# POWER.net
KiCad netlist of a schematic drawn in Altium Designer
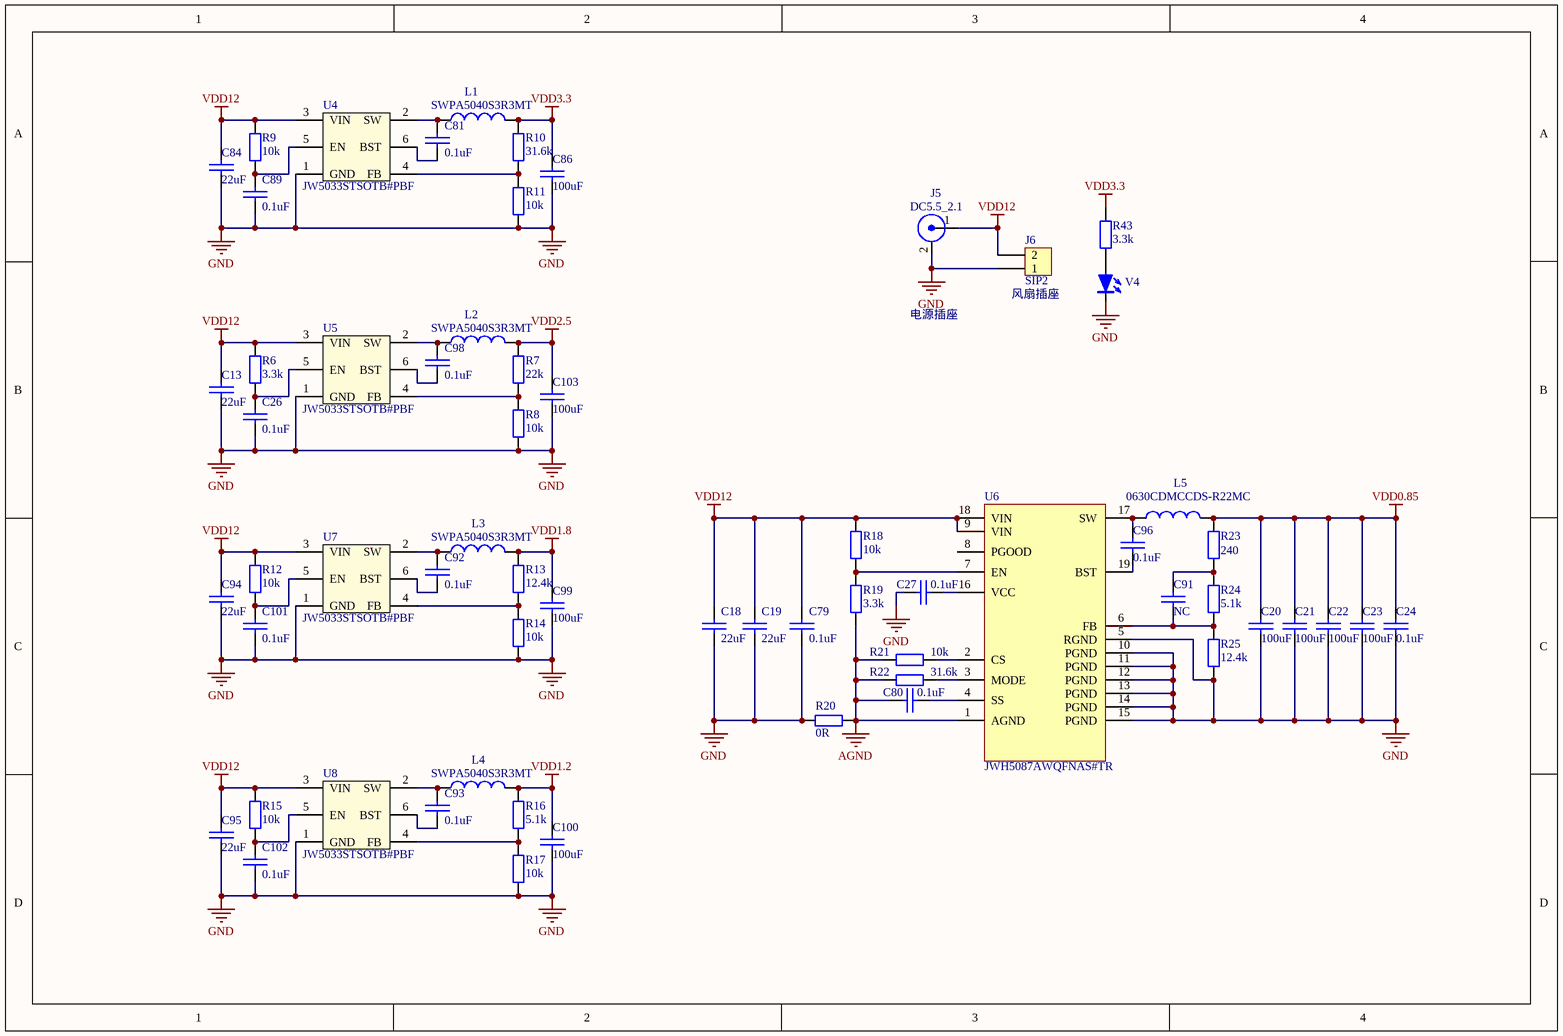
[diagram p0: POWER.SchDoc]

(export (version "E")
  (design (tool "Eeschema 10.0.6"))
  (components
    (comp (ref "C13") (value "22uF") (footprint "1210_C_M") (libsource (lib "Component") (part "CAP")))
    (comp (ref "C18") (value "22uF") (footprint "1210_C_M") (libsource (lib "Component") (part "CAP")))
    (comp (ref "C19") (value "22uF") (footprint "1210_C_M") (libsource (lib "Component") (part "CAP")))
    (comp (ref "C20") (value "100uF") (footprint "1210_C_M") (libsource (lib "Component") (part "CAP")))
    (comp (ref "C21") (value "100uF") (footprint "1210_C_M") (libsource (lib "Component") (part "CAP")))
    (comp (ref "C22") (value "100uF") (footprint "1210_C_M") (libsource (lib "Component") (part "CAP")))
    (comp (ref "C23") (value "100uF") (footprint "1210_C_M") (libsource (lib "Component") (part "CAP")))
    (comp (ref "C24") (value "0.1uF") (footprint "0402_C_M") (libsource (lib "Component") (part "CAP")))
    (comp (ref "C26") (value "0.1uF") (footprint "0402_C_M") (libsource (lib "Component") (part "CAP")))
    (comp (ref "C27") (value "0.1uF") (footprint "0402_C_M") (libsource (lib "Component") (part "CAP")))
    (comp (ref "C79") (value "0.1uF") (footprint "0402_C_M") (libsource (lib "Component") (part "CAP")))
    (comp (ref "C80") (value "0.1uF") (footprint "0402_C_M") (libsource (lib "Component") (part "CAP")))
    (comp (ref "C81") (value "0.1uF") (footprint "0402_C_M") (libsource (lib "Component") (part "CAP")))
    (comp (ref "C84") (value "22uF") (footprint "1210_C_M") (libsource (lib "Component") (part "CAP")))
    (comp (ref "C86") (value "100uF") (footprint "1210_C_M") (libsource (lib "Component") (part "CAP")))
    (comp (ref "C89") (value "0.1uF") (footprint "0402_C_M") (libsource (lib "Component") (part "CAP")))
    (comp (ref "C91") (value "NC") (footprint "0402_C_M") (libsource (lib "Component") (part "CAP")))
    (comp (ref "C92") (value "0.1uF") (footprint "0402_C_M") (libsource (lib "Component") (part "CAP")))
    (comp (ref "C93") (value "0.1uF") (footprint "0402_C_M") (libsource (lib "Component") (part "CAP")))
    (comp (ref "C94") (value "22uF") (footprint "1210_C_M") (libsource (lib "Component") (part "CAP")))
    (comp (ref "C95") (value "22uF") (footprint "1210_C_M") (libsource (lib "Component") (part "CAP")))
    (comp (ref "C96") (value "0.1uF") (footprint "0402_C_M") (libsource (lib "Component") (part "CAP")))
    (comp (ref "C98") (value "0.1uF") (footprint "0402_C_M") (libsource (lib "Component") (part "CAP")))
    (comp (ref "C99") (value "100uF") (footprint "1210_C_M") (libsource (lib "Component") (part "CAP")))
    (comp (ref "C100") (value "100uF") (footprint "1210_C_M") (libsource (lib "Component") (part "CAP")))
    (comp (ref "C101") (value "0.1uF") (footprint "0402_C_M") (libsource (lib "Component") (part "CAP")))
    (comp (ref "C102") (value "0.1uF") (footprint "0402_C_M") (libsource (lib "Component") (part "CAP")))
    (comp (ref "C103") (value "100uF") (footprint "1210_C_M") (libsource (lib "Component") (part "CAP")))
    (comp (ref "J5") (value "DC5.5_2.1") (footprint "DC5.5") (libsource (lib "常用库") (part "BNC")))
    (comp (ref "J6") (value "SIP2") (footprint "2.54mm_2p") (libsource (lib "DIP_SIP") (part "SIP2")))
    (comp (ref "L1")
      (value "SWPA5040S3R3MT")
      (footprint "CD42")
      (libsource (lib "My library") (part "INDUCTOR1"))
    )
    (comp (ref "L2")
      (value "SWPA5040S3R3MT")
      (footprint "CD42")
      (libsource (lib "My library") (part "INDUCTOR1"))
    )
    (comp (ref "L3")
      (value "SWPA5040S3R3MT")
      (footprint "CD42")
      (libsource (lib "My library") (part "INDUCTOR1"))
    )
    (comp (ref "L4")
      (value "SWPA5040S3R3MT")
      (footprint "CD42")
      (libsource (lib "My library") (part "INDUCTOR1"))
    )
    (comp (ref "L5")
      (value "0630CDMCCDS-R22MC")
      (footprint "SWPA8050S")
      (libsource (lib "My library") (part "INDUCTOR1"))
    )
    (comp (ref "R6") (value "3.3k") (footprint "0402_R_M") (libsource (lib "Common") (part "RES2")))
    (comp (ref "R7") (value "22k") (footprint "0402_R_M") (libsource (lib "Common") (part "RES2")))
    (comp (ref "R8") (value "10k") (footprint "0402_R_M") (libsource (lib "Common") (part "RES2")))
    (comp (ref "R9") (value "10k") (footprint "0402_R_M") (libsource (lib "Common") (part "RES2")))
    (comp (ref "R10") (value "31.6k") (footprint "0402_R_M") (libsource (lib "Common") (part "RES2")))
    (comp (ref "R11") (value "10k") (footprint "0402_R_M") (libsource (lib "Common") (part "RES2")))
    (comp (ref "R12") (value "10k") (footprint "0402_R_M") (libsource (lib "Common") (part "RES2")))
    (comp (ref "R13") (value "12.4k") (footprint "0402_R_M") (libsource (lib "Common") (part "RES2")))
    (comp (ref "R14") (value "10k") (footprint "0402_R_M") (libsource (lib "Common") (part "RES2")))
    (comp (ref "R15") (value "10k") (footprint "0402_R_M") (libsource (lib "Common") (part "RES2")))
    (comp (ref "R16") (value "5.1k") (footprint "0402_R_M") (libsource (lib "Common") (part "RES2")))
    (comp (ref "R17") (value "10k") (footprint "0402_R_M") (libsource (lib "Common") (part "RES2")))
    (comp (ref "R18") (value "10k") (footprint "0402_R_M") (libsource (lib "Common") (part "RES2")))
    (comp (ref "R19") (value "3.3k") (footprint "0402_R_M") (libsource (lib "Common") (part "RES2")))
    (comp (ref "R20") (value "0R") (footprint "0402_R_M") (libsource (lib "Common") (part "RES2")))
    (comp (ref "R21") (value "10k") (footprint "0402_R_M") (libsource (lib "Common") (part "RES2")))
    (comp (ref "R22") (value "31.6k") (footprint "0402_R_M") (libsource (lib "Common") (part "RES2")))
    (comp (ref "R23") (value "240") (footprint "0402_R_M") (libsource (lib "Common") (part "RES2")))
    (comp (ref "R24") (value "5.1k") (footprint "0402_R_M") (libsource (lib "Common") (part "RES2")))
    (comp (ref "R25") (value "12.4k") (footprint "0402_R_M") (libsource (lib "Common") (part "RES2")))
    (comp (ref "R43") (value "3.3k") (footprint "0402_R_M") (libsource (lib "Common") (part "RES2")))
    (comp (ref "U4")
      (value "JW5033STSOTB#PBF")
      (footprint "SOT23-6")
      (libsource (lib "XC7A35T") (part "JW5060TTSOTB#PBF"))
    )
    (comp (ref "U5")
      (value "JW5033STSOTB#PBF")
      (footprint "SOT23-6")
      (libsource (lib "XC7A35T") (part "JW5060TTSOTB#PBF"))
    )
    (comp (ref "U6") (value "JWH5087AWQFNAS#TR") (libsource (lib "POWER_1") (part "IC_JW85012")))
    (comp (ref "U7")
      (value "JW5033STSOTB#PBF")
      (footprint "SOT23-6")
      (libsource (lib "XC7A35T") (part "JW5060TTSOTB#PBF"))
    )
    (comp (ref "U8")
      (value "JW5033STSOTB#PBF")
      (footprint "SOT23-6")
      (libsource (lib "XC7A35T") (part "JW5060TTSOTB#PBF"))
    )
    (comp (ref "V4") (value "LED") (footprint "0805D") (libsource (lib "发光管、数码管") (part "LED2")))
  )
  (nets
    (net (code "1") (name "AGND") (class "Default")
      (node (ref "C80") (pin "1") (pinfunction "1_1") (pintype "passive"))
      (node (ref "R19") (pin "1") (pintype "passive"))
      (node (ref "R20") (pin "2") (pintype "passive"))
      (node (ref "R21") (pin "2") (pintype "passive"))
      (node (ref "R22") (pin "2") (pintype "passive"))
      (node (ref "U6") (pin "1") (pinfunction "AGND_1") (pintype "passive"))
    )
    (net (code "2") (name "GND") (class "Default")
      (node (ref "C100") (pin "2") (pinfunction "2_2") (pintype "passive"))
      (node (ref "C101") (pin "2") (pinfunction "2_2") (pintype "passive"))
      (node (ref "C102") (pin "2") (pinfunction "2_2") (pintype "passive"))
      (node (ref "C103") (pin "2") (pinfunction "2_2") (pintype "passive"))
      (node (ref "C13") (pin "2") (pinfunction "2_2") (pintype "passive"))
      (node (ref "C18") (pin "1") (pinfunction "1_1") (pintype "passive"))
      (node (ref "C19") (pin "1") (pinfunction "1_1") (pintype "passive"))
      (node (ref "C20") (pin "2") (pinfunction "2_2") (pintype "passive"))
      (node (ref "C21") (pin "2") (pinfunction "2_2") (pintype "passive"))
      (node (ref "C22") (pin "2") (pinfunction "2_2") (pintype "passive"))
      (node (ref "C23") (pin "2") (pinfunction "2_2") (pintype "passive"))
      (node (ref "C24") (pin "1") (pinfunction "1_1") (pintype "passive"))
      (node (ref "C26") (pin "2") (pinfunction "2_2") (pintype "passive"))
      (node (ref "C27") (pin "2") (pinfunction "2_2") (pintype "passive"))
      (node (ref "C79") (pin "2") (pinfunction "2_2") (pintype "passive"))
      (node (ref "C84") (pin "2") (pinfunction "2_2") (pintype "passive"))
      (node (ref "C86") (pin "2") (pinfunction "2_2") (pintype "passive"))
      (node (ref "C89") (pin "2") (pinfunction "2_2") (pintype "passive"))
      (node (ref "C94") (pin "2") (pinfunction "2_2") (pintype "passive"))
      (node (ref "C95") (pin "2") (pinfunction "2_2") (pintype "passive"))
      (node (ref "C99") (pin "2") (pinfunction "2_2") (pintype "passive"))
      (node (ref "J5") (pin "2") (pinfunction "2_2") (pintype "passive"))
      (node (ref "J6") (pin "1") (pinfunction "1_1") (pintype "passive"))
      (node (ref "R11") (pin "2") (pintype "passive"))
      (node (ref "R14") (pin "2") (pintype "passive"))
      (node (ref "R17") (pin "2") (pintype "passive"))
      (node (ref "R20") (pin "1") (pintype "passive"))
      (node (ref "R25") (pin "2") (pintype "passive"))
      (node (ref "R8") (pin "2") (pintype "passive"))
      (node (ref "U4") (pin "1") (pinfunction "GND_1") (pintype "passive"))
      (node (ref "U5") (pin "1") (pinfunction "GND_1") (pintype "passive"))
      (node (ref "U6") (pin "10") (pinfunction "PGND_10") (pintype "passive"))
      (node (ref "U6") (pin "11") (pinfunction "PGND_11") (pintype "passive"))
      (node (ref "U6") (pin "12") (pinfunction "PGND_12") (pintype "passive"))
      (node (ref "U6") (pin "13") (pinfunction "PGND_13") (pintype "passive"))
      (node (ref "U6") (pin "14") (pinfunction "PGND_14") (pintype "passive"))
      (node (ref "U6") (pin "15") (pinfunction "PGND_15") (pintype "passive"))
      (node (ref "U6") (pin "5") (pinfunction "RGND_5") (pintype "passive"))
      (node (ref "U7") (pin "1") (pinfunction "GND_1") (pintype "passive"))
      (node (ref "U8") (pin "1") (pinfunction "GND_1") (pintype "passive"))
      (node (ref "V4") (pin "2") (pinfunction "2_2") (pintype "passive"))
    )
    (net (code "3") (name "Net-(C91-Pad2)") (class "Default")
      (node (ref "C91") (pin "2") (pinfunction "2_2") (pintype "passive"))
      (node (ref "R23") (pin "2") (pintype "passive"))
      (node (ref "R24") (pin "1") (pintype "passive"))
    )
    (net (code "4") (name "Net-(R43-Pad1)") (class "Default")
      (node (ref "R43") (pin "1") (pintype "passive"))
      (node (ref "V4") (pin "1") (pinfunction "1_1") (pintype "passive"))
    )
    (net (code "5") (name "Net-(U4-BST)") (class "Default")
      (node (ref "C81") (pin "1") (pinfunction "1_1") (pintype "passive"))
      (node (ref "U4") (pin "6") (pinfunction "BST_6") (pintype "passive"))
    )
    (net (code "6") (name "Net-(U4-EN)") (class "Default")
      (node (ref "C89") (pin "1") (pinfunction "1_1") (pintype "passive"))
      (node (ref "R9") (pin "1") (pintype "passive"))
      (node (ref "U4") (pin "5") (pinfunction "EN_5") (pintype "passive"))
    )
    (net (code "7") (name "Net-(U4-FB)") (class "Default")
      (node (ref "R10") (pin "1") (pintype "passive"))
      (node (ref "R11") (pin "1") (pintype "passive"))
      (node (ref "U4") (pin "4") (pinfunction "FB_4") (pintype "passive"))
    )
    (net (code "8") (name "Net-(U4-SW)") (class "Default")
      (node (ref "C81") (pin "2") (pinfunction "2_2") (pintype "passive"))
      (node (ref "L1") (pin "1") (pinfunction "1_1") (pintype "passive"))
      (node (ref "U4") (pin "2") (pinfunction "SW_2") (pintype "passive"))
    )
    (net (code "9") (name "Net-(U5-BST)") (class "Default")
      (node (ref "C98") (pin "1") (pinfunction "1_1") (pintype "passive"))
      (node (ref "U5") (pin "6") (pinfunction "BST_6") (pintype "passive"))
    )
    (net (code "10") (name "Net-(U5-EN)") (class "Default")
      (node (ref "C26") (pin "1") (pinfunction "1_1") (pintype "passive"))
      (node (ref "R6") (pin "1") (pintype "passive"))
      (node (ref "U5") (pin "5") (pinfunction "EN_5") (pintype "passive"))
    )
    (net (code "11") (name "Net-(U5-FB)") (class "Default")
      (node (ref "R7") (pin "1") (pintype "passive"))
      (node (ref "R8") (pin "1") (pintype "passive"))
      (node (ref "U5") (pin "4") (pinfunction "FB_4") (pintype "passive"))
    )
    (net (code "12") (name "Net-(U5-SW)") (class "Default")
      (node (ref "C98") (pin "2") (pinfunction "2_2") (pintype "passive"))
      (node (ref "L2") (pin "1") (pinfunction "1_1") (pintype "passive"))
      (node (ref "U5") (pin "2") (pinfunction "SW_2") (pintype "passive"))
    )
    (net (code "13") (name "Net-(U6-BST)") (class "Default")
      (node (ref "C96") (pin "1") (pinfunction "1_1") (pintype "passive"))
      (node (ref "U6") (pin "19") (pinfunction "BST_19") (pintype "passive"))
    )
    (net (code "14") (name "Net-(U6-CS)") (class "Default")
      (node (ref "R21") (pin "1") (pintype "passive"))
      (node (ref "U6") (pin "2") (pinfunction "CS_2") (pintype "passive"))
    )
    (net (code "15") (name "Net-(U6-EN)") (class "Default")
      (node (ref "R18") (pin "2") (pintype "passive"))
      (node (ref "R19") (pin "2") (pintype "passive"))
      (node (ref "U6") (pin "7") (pinfunction "EN_7") (pintype "passive"))
    )
    (net (code "16") (name "Net-(U6-FB)") (class "Default")
      (node (ref "C91") (pin "1") (pinfunction "1_1") (pintype "passive"))
      (node (ref "R24") (pin "2") (pintype "passive"))
      (node (ref "R25") (pin "1") (pintype "passive"))
      (node (ref "U6") (pin "6") (pinfunction "FB_6") (pintype "passive"))
    )
    (net (code "17") (name "Net-(U6-MODE)") (class "Default")
      (node (ref "R22") (pin "1") (pintype "passive"))
      (node (ref "U6") (pin "3") (pinfunction "MODE_3") (pintype "passive"))
    )
    (net (code "18") (name "Net-(U6-SS)") (class "Default")
      (node (ref "C80") (pin "2") (pinfunction "2_2") (pintype "passive"))
      (node (ref "U6") (pin "4") (pinfunction "SS_4") (pintype "passive"))
    )
    (net (code "19") (name "Net-(U6-SW)") (class "Default")
      (node (ref "C96") (pin "2") (pinfunction "2_2") (pintype "passive"))
      (node (ref "L5") (pin "1") (pinfunction "1_1") (pintype "passive"))
      (node (ref "U6") (pin "17") (pinfunction "SW_17") (pintype "passive"))
    )
    (net (code "20") (name "Net-(U6-VCC)") (class "Default")
      (node (ref "C27") (pin "1") (pinfunction "1_1") (pintype "passive"))
      (node (ref "U6") (pin "16") (pinfunction "VCC_16") (pintype "passive"))
    )
    (net (code "21") (name "Net-(U7-BST)") (class "Default")
      (node (ref "C92") (pin "1") (pinfunction "1_1") (pintype "passive"))
      (node (ref "U7") (pin "6") (pinfunction "BST_6") (pintype "passive"))
    )
    (net (code "22") (name "Net-(U7-EN)") (class "Default")
      (node (ref "C101") (pin "1") (pinfunction "1_1") (pintype "passive"))
      (node (ref "R12") (pin "1") (pintype "passive"))
      (node (ref "U7") (pin "5") (pinfunction "EN_5") (pintype "passive"))
    )
    (net (code "23") (name "Net-(U7-FB)") (class "Default")
      (node (ref "R13") (pin "1") (pintype "passive"))
      (node (ref "R14") (pin "1") (pintype "passive"))
      (node (ref "U7") (pin "4") (pinfunction "FB_4") (pintype "passive"))
    )
    (net (code "24") (name "Net-(U7-SW)") (class "Default")
      (node (ref "C92") (pin "2") (pinfunction "2_2") (pintype "passive"))
      (node (ref "L3") (pin "1") (pinfunction "1_1") (pintype "passive"))
      (node (ref "U7") (pin "2") (pinfunction "SW_2") (pintype "passive"))
    )
    (net (code "25") (name "Net-(U8-BST)") (class "Default")
      (node (ref "C93") (pin "1") (pinfunction "1_1") (pintype "passive"))
      (node (ref "U8") (pin "6") (pinfunction "BST_6") (pintype "passive"))
    )
    (net (code "26") (name "Net-(U8-EN)") (class "Default")
      (node (ref "C102") (pin "1") (pinfunction "1_1") (pintype "passive"))
      (node (ref "R15") (pin "1") (pintype "passive"))
      (node (ref "U8") (pin "5") (pinfunction "EN_5") (pintype "passive"))
    )
    (net (code "27") (name "Net-(U8-FB)") (class "Default")
      (node (ref "R16") (pin "1") (pintype "passive"))
      (node (ref "R17") (pin "1") (pintype "passive"))
      (node (ref "U8") (pin "4") (pinfunction "FB_4") (pintype "passive"))
    )
    (net (code "28") (name "Net-(U8-SW)") (class "Default")
      (node (ref "C93") (pin "2") (pinfunction "2_2") (pintype "passive"))
      (node (ref "L4") (pin "1") (pinfunction "1_1") (pintype "passive"))
      (node (ref "U8") (pin "2") (pinfunction "SW_2") (pintype "passive"))
    )
    (net (code "29") (name "VDD0.85") (class "Default")
      (node (ref "C20") (pin "1") (pinfunction "1_1") (pintype "passive"))
      (node (ref "C21") (pin "1") (pinfunction "1_1") (pintype "passive"))
      (node (ref "C22") (pin "1") (pinfunction "1_1") (pintype "passive"))
      (node (ref "C23") (pin "1") (pinfunction "1_1") (pintype "passive"))
      (node (ref "C24") (pin "2") (pinfunction "2_2") (pintype "passive"))
      (node (ref "L5") (pin "2") (pinfunction "2_2") (pintype "passive"))
      (node (ref "R23") (pin "1") (pintype "passive"))
    )
    (net (code "30") (name "VDD1.2") (class "Default")
      (node (ref "C100") (pin "1") (pinfunction "1_1") (pintype "passive"))
      (node (ref "L4") (pin "2") (pinfunction "2_2") (pintype "passive"))
      (node (ref "R16") (pin "2") (pintype "passive"))
    )
    (net (code "31") (name "VDD1.8") (class "Default")
      (node (ref "C99") (pin "1") (pinfunction "1_1") (pintype "passive"))
      (node (ref "L3") (pin "2") (pinfunction "2_2") (pintype "passive"))
      (node (ref "R13") (pin "2") (pintype "passive"))
    )
    (net (code "32") (name "VDD2.5") (class "Default")
      (node (ref "C103") (pin "1") (pinfunction "1_1") (pintype "passive"))
      (node (ref "L2") (pin "2") (pinfunction "2_2") (pintype "passive"))
      (node (ref "R7") (pin "2") (pintype "passive"))
    )
    (net (code "33") (name "VDD3.3") (class "Default")
      (node (ref "C86") (pin "1") (pinfunction "1_1") (pintype "passive"))
      (node (ref "L1") (pin "2") (pinfunction "2_2") (pintype "passive"))
      (node (ref "R10") (pin "2") (pintype "passive"))
      (node (ref "R43") (pin "2") (pintype "passive"))
    )
    (net (code "34") (name "VDD12") (class "Default")
      (node (ref "C13") (pin "1") (pinfunction "1_1") (pintype "passive"))
      (node (ref "C18") (pin "2") (pinfunction "2_2") (pintype "passive"))
      (node (ref "C19") (pin "2") (pinfunction "2_2") (pintype "passive"))
      (node (ref "C79") (pin "1") (pinfunction "1_1") (pintype "passive"))
      (node (ref "C84") (pin "1") (pinfunction "1_1") (pintype "passive"))
      (node (ref "C94") (pin "1") (pinfunction "1_1") (pintype "passive"))
      (node (ref "C95") (pin "1") (pinfunction "1_1") (pintype "passive"))
      (node (ref "J5") (pin "1") (pinfunction "1_1") (pintype "passive"))
      (node (ref "J6") (pin "2") (pinfunction "2_2") (pintype "passive"))
      (node (ref "R12") (pin "2") (pintype "passive"))
      (node (ref "R15") (pin "2") (pintype "passive"))
      (node (ref "R18") (pin "1") (pintype "passive"))
      (node (ref "R6") (pin "2") (pintype "passive"))
      (node (ref "R9") (pin "2") (pintype "passive"))
      (node (ref "U4") (pin "3") (pinfunction "VIN_3") (pintype "passive"))
      (node (ref "U5") (pin "3") (pinfunction "VIN_3") (pintype "passive"))
      (node (ref "U6") (pin "18") (pinfunction "VIN_18") (pintype "passive"))
      (node (ref "U6") (pin "9") (pinfunction "VIN_9") (pintype "passive"))
      (node (ref "U7") (pin "3") (pinfunction "VIN_3") (pintype "passive"))
      (node (ref "U8") (pin "3") (pinfunction "VIN_3") (pintype "passive"))
    )
    (net (code "35") (name "unconnected-(U6-PGOOD-Pad8)") (class "Default")
      (node (ref "U6") (pin "8") (pinfunction "PGOOD_8") (pintype "passive"))
    )
  )
)
